# Main.net
KiCad netlist of a schematic drawn in Altium Designer
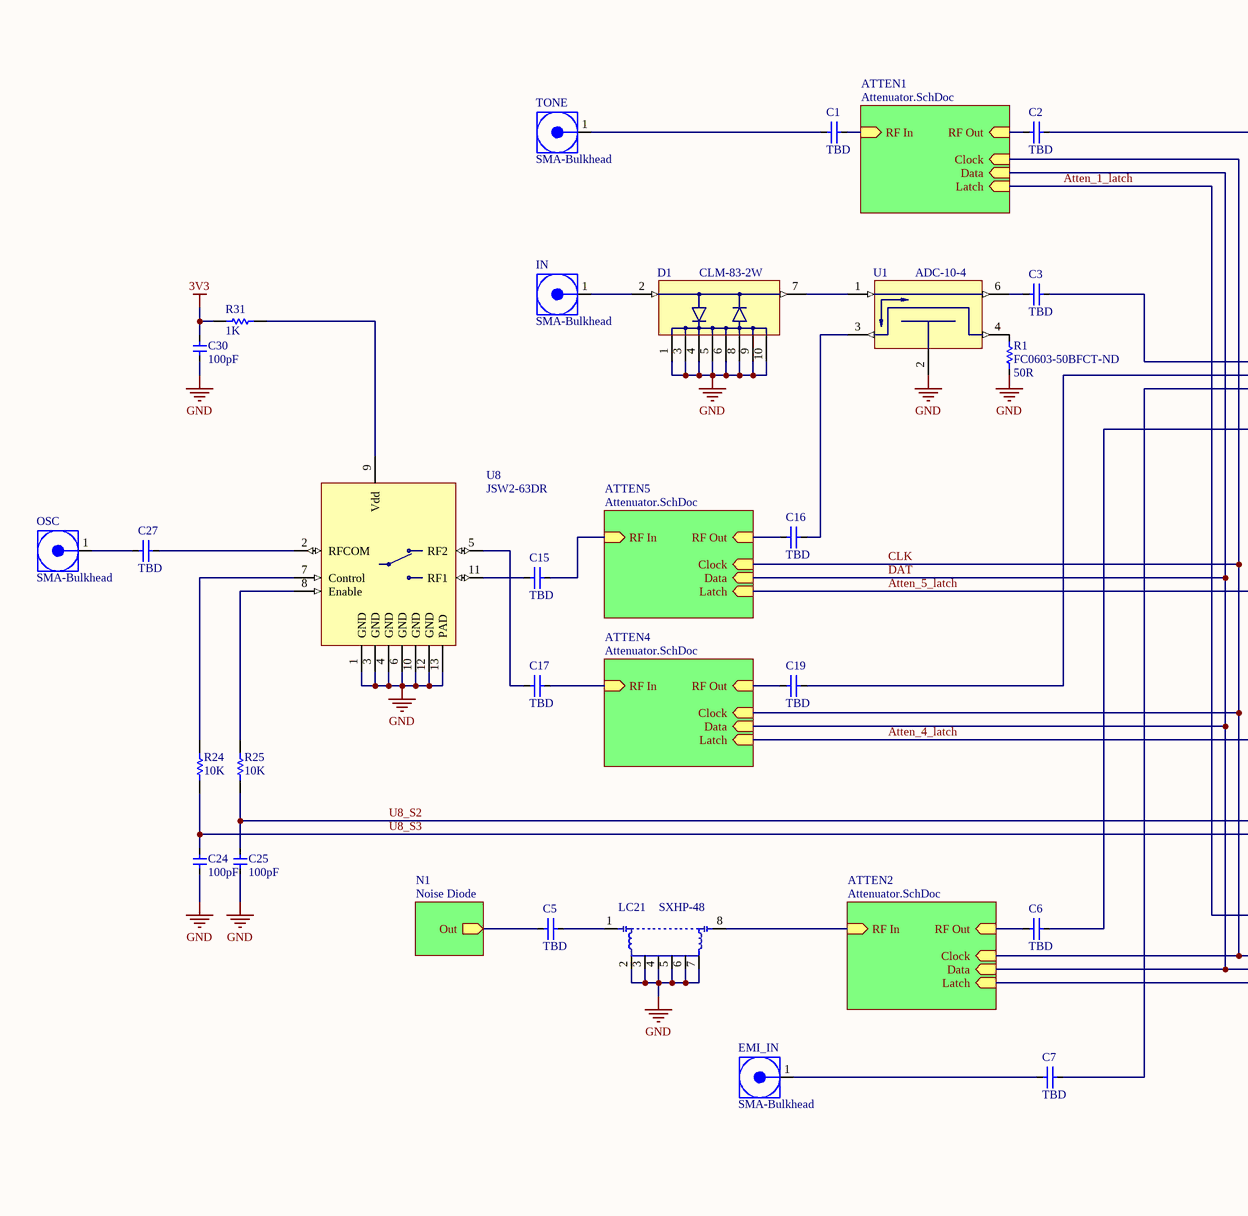
[diagram p0: Main.SchDoc, left]
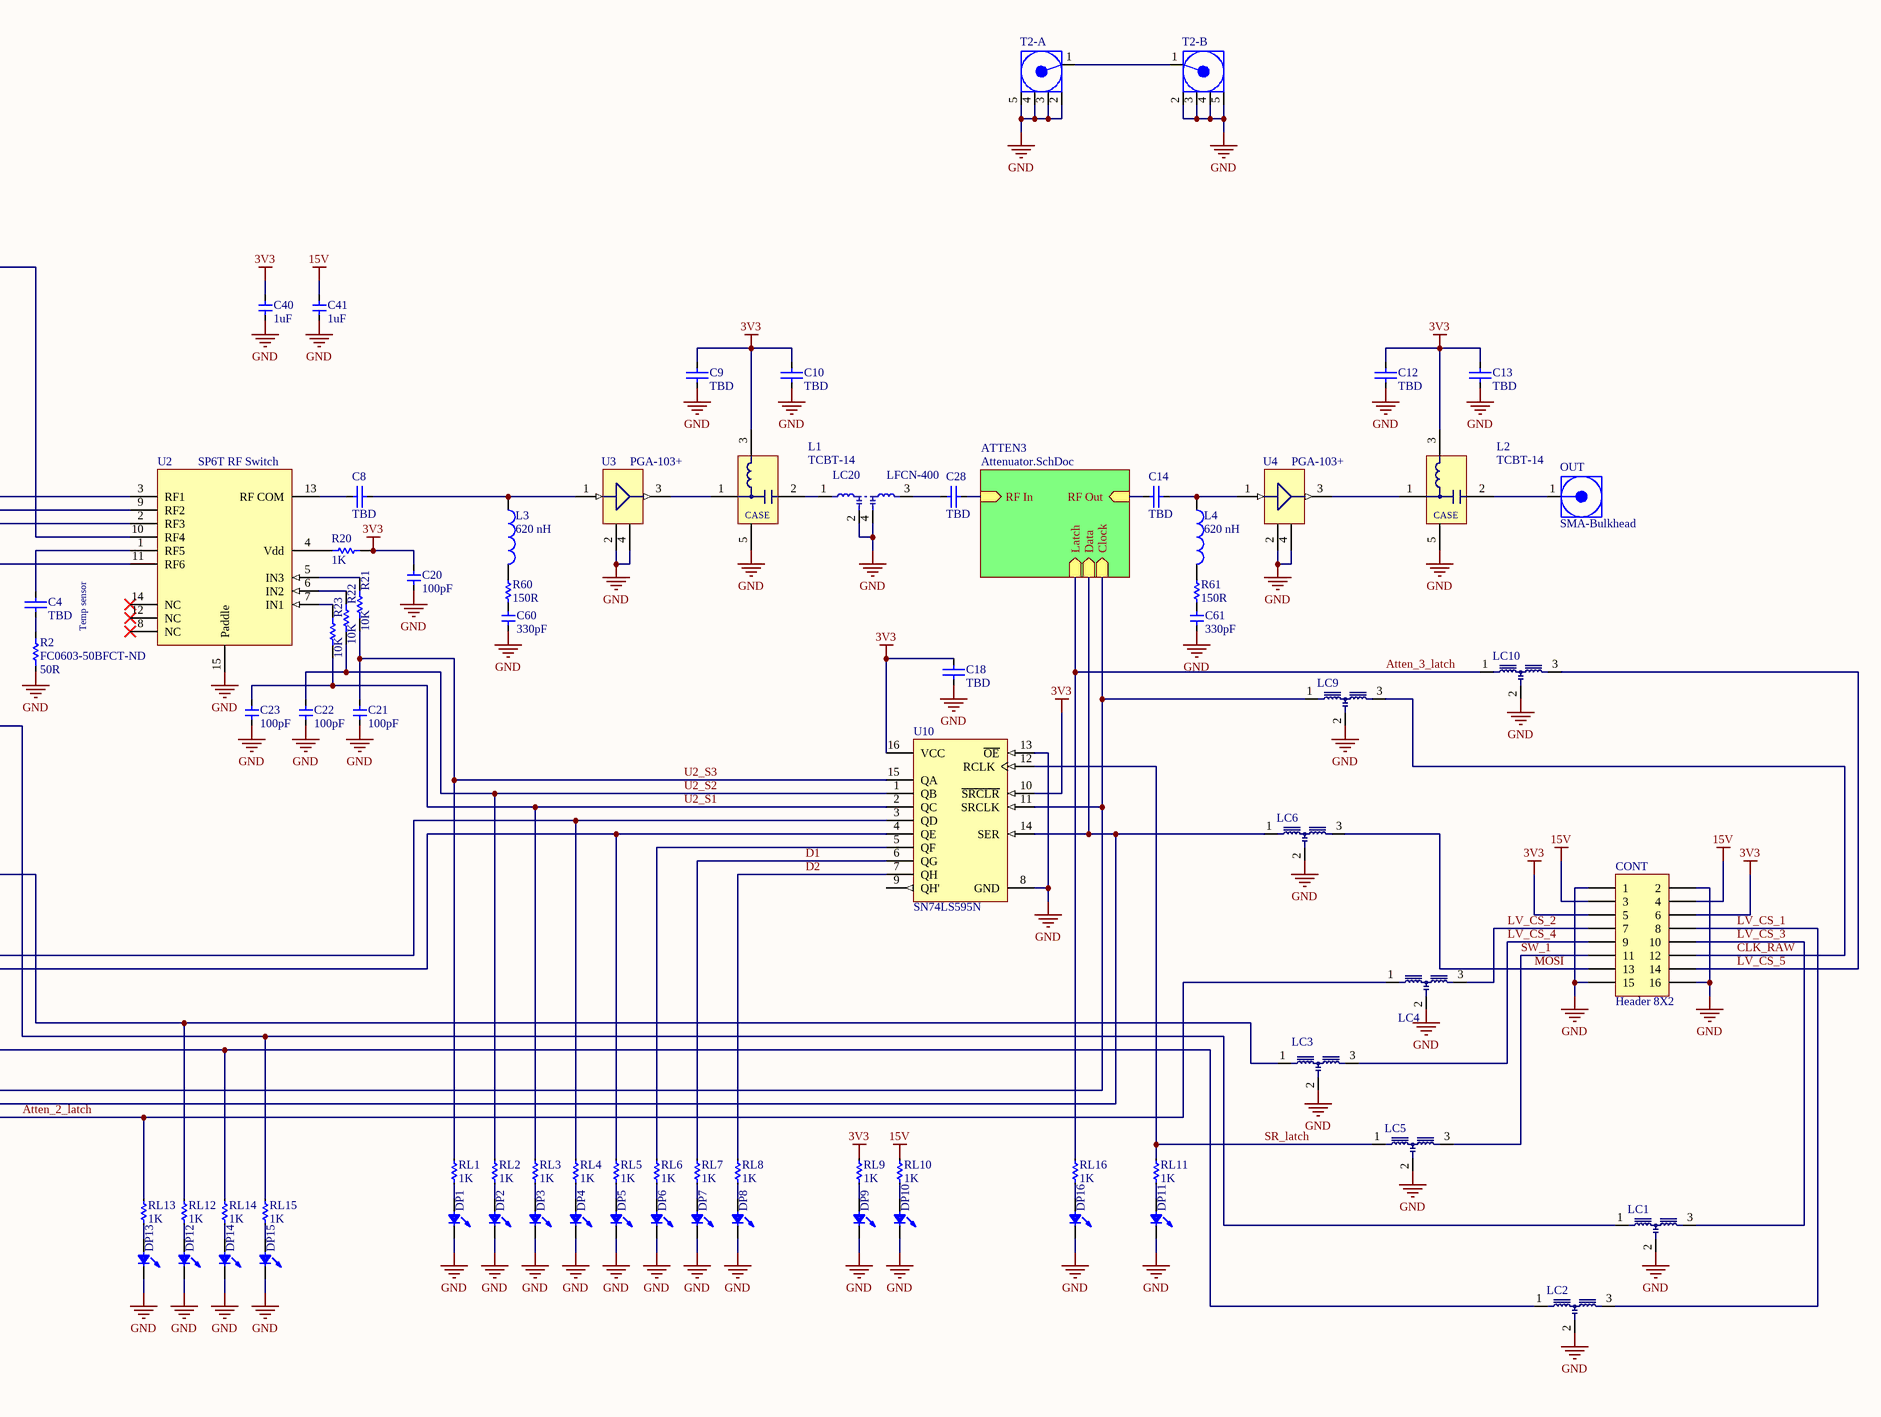
[diagram p1: Main.SchDoc, right]

(export (version "E")
  (design (tool "Eeschema 10.0.6"))
  (components
    (comp (ref "C1")
      (value "TBD")
      (footprint "0402C")
      (description "Capacitor")
      (fields (field (name "Comment") "Cap") (field (name "PUBLISHER") "Altium Limited"))
      (libsource (lib "Miscellaneous Devices") (part "Cap"))
    )
    (comp (ref "C2")
      (value "TBD")
      (footprint "0402C")
      (description "Capacitor")
      (fields (field (name "Comment") "Cap") (field (name "PUBLISHER") "Altium Limited"))
      (libsource (lib "Miscellaneous Devices") (part "Cap"))
    )
    (comp (ref "C3")
      (value "TBD")
      (footprint "0402C")
      (description "Capacitor")
      (fields (field (name "Comment") "Cap") (field (name "PUBLISHER") "Altium Limited"))
      (libsource (lib "Miscellaneous Devices") (part "Cap"))
    )
    (comp (ref "C4")
      (value "TBD")
      (footprint "0402C")
      (description "Capacitor")
      (fields (field (name "Comment") "Cap") (field (name "PUBLISHER") "Altium Limited"))
      (libsource (lib "Miscellaneous Devices") (part "Cap"))
    )
    (comp (ref "C5")
      (value "TBD")
      (footprint "0402C")
      (description "Capacitor")
      (fields (field (name "Comment") "Cap") (field (name "PUBLISHER") "Altium Limited"))
      (libsource (lib "Miscellaneous Devices") (part "Cap"))
    )
    (comp (ref "C6")
      (value "TBD")
      (footprint "0402C")
      (description "Capacitor")
      (fields (field (name "Comment") "Cap") (field (name "PUBLISHER") "Altium Limited"))
      (libsource (lib "Miscellaneous Devices") (part "Cap"))
    )
    (comp (ref "C7")
      (value "TBD")
      (footprint "0402C")
      (description "Capacitor")
      (fields (field (name "Comment") "Cap") (field (name "PUBLISHER") "Altium Limited"))
      (libsource (lib "Miscellaneous Devices") (part "Cap"))
    )
    (comp (ref "C8")
      (value "TBD")
      (footprint "0402C")
      (description "Capacitor")
      (fields (field (name "Comment") "Cap") (field (name "PUBLISHER") "Altium Limited"))
      (libsource (lib "Miscellaneous Devices") (part "Cap"))
    )
    (comp (ref "C9")
      (value "TBD")
      (footprint "0805C")
      (description "Capacitor")
      (fields (field (name "Comment") "Cap") (field (name "PUBLISHER") "Altium Limited"))
      (libsource (lib "Miscellaneous Devices") (part "Cap"))
    )
    (comp (ref "C10")
      (value "TBD")
      (footprint "0805C")
      (description "Capacitor")
      (fields (field (name "Comment") "Cap") (field (name "PUBLISHER") "Altium Limited"))
      (libsource (lib "Miscellaneous Devices") (part "Cap"))
    )
    (comp (ref "C12")
      (value "TBD")
      (footprint "0805C")
      (description "Capacitor")
      (fields (field (name "Comment") "Cap") (field (name "PUBLISHER") "Altium Limited"))
      (libsource (lib "Miscellaneous Devices") (part "Cap"))
    )
    (comp (ref "C13")
      (value "TBD")
      (footprint "0805C")
      (description "Capacitor")
      (fields (field (name "Comment") "Cap") (field (name "PUBLISHER") "Altium Limited"))
      (libsource (lib "Miscellaneous Devices") (part "Cap"))
    )
    (comp (ref "C14")
      (value "TBD")
      (footprint "0402C")
      (description "Capacitor")
      (fields (field (name "Comment") "Cap") (field (name "PUBLISHER") "Altium Limited"))
      (libsource (lib "Miscellaneous Devices") (part "Cap"))
    )
    (comp (ref "C15")
      (value "TBD")
      (footprint "0402C")
      (description "Capacitor")
      (fields (field (name "Comment") "Cap") (field (name "PUBLISHER") "Altium Limited"))
      (libsource (lib "Miscellaneous Devices") (part "Cap"))
    )
    (comp (ref "C16")
      (value "TBD")
      (footprint "0402C")
      (description "Capacitor")
      (fields (field (name "Comment") "Cap") (field (name "PUBLISHER") "Altium Limited"))
      (libsource (lib "Miscellaneous Devices") (part "Cap"))
    )
    (comp (ref "C17")
      (value "TBD")
      (footprint "0402C")
      (description "Capacitor")
      (fields (field (name "Comment") "Cap") (field (name "PUBLISHER") "Altium Limited"))
      (libsource (lib "Miscellaneous Devices") (part "Cap"))
    )
    (comp (ref "C18")
      (value "TBD")
      (footprint "0603C")
      (description "Capacitor")
      (fields (field (name "Comment") "Cap") (field (name "PUBLISHER") "Altium Limited"))
      (libsource (lib "Miscellaneous Devices") (part "Cap"))
    )
    (comp (ref "C19")
      (value "TBD")
      (footprint "0402C")
      (description "Capacitor")
      (fields (field (name "Comment") "Cap") (field (name "PUBLISHER") "Altium Limited"))
      (libsource (lib "Miscellaneous Devices") (part "Cap"))
    )
    (comp (ref "C20")
      (value "100pF")
      (footprint "0603C")
      (description "SMT Cap")
      (fields (field (name "PUBLISHER") "Altium Limited"))
      (libsource (lib "Miscellaneous Devices") (part "Cap - SMT Small"))
    )
    (comp (ref "C21")
      (value "100pF")
      (footprint "0603C")
      (description "SMT Cap")
      (fields (field (name "PUBLISHER") "Altium Limited"))
      (libsource (lib "Miscellaneous Devices") (part "Cap - SMT Small"))
    )
    (comp (ref "C22")
      (value "100pF")
      (footprint "0603C")
      (description "SMT Cap")
      (fields (field (name "PUBLISHER") "Altium Limited"))
      (libsource (lib "Miscellaneous Devices") (part "Cap - SMT Small"))
    )
    (comp (ref "C23")
      (value "100pF")
      (footprint "0603C")
      (description "SMT Cap")
      (fields (field (name "PUBLISHER") "Altium Limited"))
      (libsource (lib "Miscellaneous Devices") (part "Cap - SMT Small"))
    )
    (comp (ref "C24")
      (value "100pF")
      (footprint "0603C")
      (description "SMT Cap")
      (fields (field (name "PUBLISHER") "Altium Limited"))
      (libsource (lib "Miscellaneous Devices") (part "Cap - SMT Small"))
    )
    (comp (ref "C25")
      (value "100pF")
      (footprint "0603C")
      (description "SMT Cap")
      (fields (field (name "PUBLISHER") "Altium Limited"))
      (libsource (lib "Miscellaneous Devices") (part "Cap - SMT Small"))
    )
    (comp (ref "C27")
      (value "TBD")
      (footprint "0402C")
      (description "Capacitor")
      (fields (field (name "Comment") "Cap") (field (name "PUBLISHER") "Altium Limited"))
      (libsource (lib "Miscellaneous Devices") (part "Cap"))
    )
    (comp (ref "C28")
      (value "TBD")
      (footprint "0402C")
      (description "Capacitor")
      (fields (field (name "Comment") "Cap") (field (name "PUBLISHER") "Altium Limited"))
      (libsource (lib "Miscellaneous Devices") (part "Cap"))
    )
    (comp (ref "C30")
      (value "100pF")
      (footprint "0603C")
      (description "SMT Cap")
      (fields (field (name "PUBLISHER") "Altium Limited"))
      (libsource (lib "Miscellaneous Devices") (part "Cap - SMT Small"))
    )
    (comp (ref "C40")
      (value "1uF")
      (footprint "V")
      (description "SMT Cap")
      (fields (field (name "PUBLISHER") "Altium Limited"))
      (libsource (lib "Miscellaneous Devices") (part "Cap - SMT Small"))
    )
    (comp (ref "C41")
      (value "1uF")
      (footprint "V")
      (description "SMT Cap")
      (fields (field (name "PUBLISHER") "Altium Limited"))
      (libsource (lib "Miscellaneous Devices") (part "Cap - SMT Small"))
    )
    (comp (ref "C60")
      (value "330pF")
      (footprint "0603C")
      (description "SMT Cap")
      (fields (field (name "PUBLISHER") "Altium Limited"))
      (libsource (lib "Miscellaneous Devices") (part "Cap - SMT Small"))
    )
    (comp (ref "C61")
      (value "330pF")
      (footprint "0603C")
      (description "SMT Cap")
      (fields (field (name "PUBLISHER") "Altium Limited"))
      (libsource (lib "Miscellaneous Devices") (part "Cap - SMT Small"))
    )
    (comp (ref "CONT")
      (value "Header 8X2")
      (footprint "5103310-3")
      (description "Header, 8-Pin, Dual row")
      (fields (field (name "PUBLISHER") "Altium Limited"))
      (libsource (lib "Miscellaneous Connectors") (part "Header 8X2"))
    )
    (comp (ref "D1")
      (value "CLM-83-2W")
      (footprint "DL1721")
      (description "+12 to +32 dBm RF Limiter")
      (libsource (lib "RF Components") (part "CLM-83-2W"))
    )
    (comp (ref "DP1")
      (value "LED0")
      (footprint "0603 SMT LED")
      (description "T 1 3/4 LED")
      (fields (field (name "PUBLISHER") "Altium Limited"))
      (libsource (lib "Miscellaneous Devices") (part "LED0"))
    )
    (comp (ref "DP2")
      (value "LED0")
      (footprint "0603 SMT LED")
      (description "T 1 3/4 LED")
      (fields (field (name "PUBLISHER") "Altium Limited"))
      (libsource (lib "Miscellaneous Devices") (part "LED0"))
    )
    (comp (ref "DP3")
      (value "LED0")
      (footprint "0603 SMT LED")
      (description "T 1 3/4 LED")
      (fields (field (name "PUBLISHER") "Altium Limited"))
      (libsource (lib "Miscellaneous Devices") (part "LED0"))
    )
    (comp (ref "DP4")
      (value "LED0")
      (footprint "0603 SMT LED")
      (description "T 1 3/4 LED")
      (fields (field (name "PUBLISHER") "Altium Limited"))
      (libsource (lib "Miscellaneous Devices") (part "LED0"))
    )
    (comp (ref "DP5")
      (value "LED0")
      (footprint "0603 SMT LED")
      (description "T 1 3/4 LED")
      (fields (field (name "PUBLISHER") "Altium Limited"))
      (libsource (lib "Miscellaneous Devices") (part "LED0"))
    )
    (comp (ref "DP6")
      (value "LED0")
      (footprint "0603 SMT LED")
      (description "T 1 3/4 LED")
      (fields (field (name "PUBLISHER") "Altium Limited"))
      (libsource (lib "Miscellaneous Devices") (part "LED0"))
    )
    (comp (ref "DP7")
      (value "LED0")
      (footprint "0603 SMT LED")
      (description "T 1 3/4 LED")
      (fields (field (name "PUBLISHER") "Altium Limited"))
      (libsource (lib "Miscellaneous Devices") (part "LED0"))
    )
    (comp (ref "DP8")
      (value "LED0")
      (footprint "0603 SMT LED")
      (description "T 1 3/4 LED")
      (fields (field (name "PUBLISHER") "Altium Limited"))
      (libsource (lib "Miscellaneous Devices") (part "LED0"))
    )
    (comp (ref "DP9")
      (value "LED0")
      (footprint "0603 SMT LED")
      (description "T 1 3/4 LED")
      (fields (field (name "PUBLISHER") "Altium Limited"))
      (libsource (lib "Miscellaneous Devices") (part "LED0"))
    )
    (comp (ref "DP10")
      (value "LED0")
      (footprint "0603 SMT LED")
      (description "T 1 3/4 LED")
      (fields (field (name "PUBLISHER") "Altium Limited"))
      (libsource (lib "Miscellaneous Devices") (part "LED0"))
    )
    (comp (ref "DP11")
      (value "LED0")
      (footprint "0603 SMT LED")
      (description "T 1 3/4 LED")
      (fields (field (name "PUBLISHER") "Altium Limited"))
      (libsource (lib "Miscellaneous Devices") (part "LED0"))
    )
    (comp (ref "DP12")
      (value "LED0")
      (footprint "0603 SMT LED")
      (description "T 1 3/4 LED")
      (fields (field (name "PUBLISHER") "Altium Limited"))
      (libsource (lib "Miscellaneous Devices") (part "LED0"))
    )
    (comp (ref "DP13")
      (value "LED0")
      (footprint "0603 SMT LED")
      (description "T 1 3/4 LED")
      (fields (field (name "PUBLISHER") "Altium Limited"))
      (libsource (lib "Miscellaneous Devices") (part "LED0"))
    )
    (comp (ref "DP14")
      (value "LED0")
      (footprint "0603 SMT LED")
      (description "T 1 3/4 LED")
      (fields (field (name "PUBLISHER") "Altium Limited"))
      (libsource (lib "Miscellaneous Devices") (part "LED0"))
    )
    (comp (ref "DP15")
      (value "LED0")
      (footprint "0603 SMT LED")
      (description "T 1 3/4 LED")
      (fields (field (name "PUBLISHER") "Altium Limited"))
      (libsource (lib "Miscellaneous Devices") (part "LED0"))
    )
    (comp (ref "DP16")
      (value "LED0")
      (footprint "0603 SMT LED")
      (description "T 1 3/4 LED")
      (fields (field (name "PUBLISHER") "Altium Limited"))
      (libsource (lib "Miscellaneous Devices") (part "LED0"))
    )
    (comp (ref "EMI_IN")
      (value "SMA-Bulkhead")
      (footprint "1052902-1")
      (description "SMA Connector - Bulkhead")
      (libsource (lib "RF Components") (part "SMA-Bulkhead"))
    )
    (comp (ref "IN")
      (value "SMA-Bulkhead")
      (footprint "1052902-1")
      (description "SMA Connector - Bulkhead")
      (libsource (lib "RF Components") (part "SMA-Bulkhead"))
    )
    (comp (ref "L1")
      (value "TCBT-14")
      (footprint "GU1414")
      (description "Surface Mount 10 MHz to 10 GHz Bias Tee")
      (libsource (lib "RF Components") (part "TCBT-14"))
    )
    (comp (ref "L2")
      (value "TCBT-14")
      (footprint "GU1414")
      (description "Surface Mount 10 MHz to 10 GHz Bias Tee")
      (libsource (lib "RF Components") (part "TCBT-14"))
    )
    (comp (ref "L3")
      (value "620 nH")
      (footprint "1008L")
      (description "Inductor")
      (fields (field (name "PUBLISHER") "Altium Limited"))
      (libsource (lib "Miscellaneous Devices") (part "Inductor"))
    )
    (comp (ref "L4")
      (value "620 nH")
      (footprint "1008L")
      (description "Inductor")
      (fields (field (name "PUBLISHER") "Altium Limited"))
      (libsource (lib "Miscellaneous Devices") (part "Inductor"))
    )
    (comp (ref "LC1")
      (value "MEM2012F")
      (footprint "MEM2012S LC Filter")
      (description "Signal Line 3-terminal Filters")
      (libsource (lib "Unsorted") (part "MEM2012F - Signal Filter"))
    )
    (comp (ref "LC2")
      (value "MEM2012F")
      (footprint "MEM2012S LC Filter")
      (description "Signal Line 3-terminal Filters")
      (libsource (lib "Unsorted") (part "MEM2012F - Signal Filter"))
    )
    (comp (ref "LC3")
      (value "MEM2012F")
      (footprint "MEM2012S LC Filter")
      (description "Signal Line 3-terminal Filters")
      (libsource (lib "Unsorted") (part "MEM2012F - Signal Filter"))
    )
    (comp (ref "LC4")
      (value "MEM2012F")
      (footprint "MEM2012S LC Filter")
      (description "Signal Line 3-terminal Filters")
      (libsource (lib "Unsorted") (part "MEM2012F - Signal Filter"))
    )
    (comp (ref "LC5")
      (value "MEM2012F")
      (footprint "MEM2012S LC Filter")
      (description "Signal Line 3-terminal Filters")
      (libsource (lib "Unsorted") (part "MEM2012F - Signal Filter"))
    )
    (comp (ref "LC6")
      (value "MEM2012F")
      (footprint "MEM2012S LC Filter")
      (description "Signal Line 3-terminal Filters")
      (libsource (lib "Unsorted") (part "MEM2012F - Signal Filter"))
    )
    (comp (ref "LC9")
      (value "MEM2012F")
      (footprint "MEM2012S LC Filter")
      (description "Signal Line 3-terminal Filters")
      (libsource (lib "Unsorted") (part "MEM2012F - Signal Filter"))
    )
    (comp (ref "LC10")
      (value "MEM2012F")
      (footprint "MEM2012S LC Filter")
      (description "Signal Line 3-terminal Filters")
      (libsource (lib "Unsorted") (part "MEM2012F - Signal Filter"))
    )
    (comp (ref "LC20")
      (value "LFCN-400")
      (footprint "FV1206")
      (description "Ceramic Low Pass Filter")
      (libsource (lib "RF Components") (part "LFCN-xxx Filter"))
    )
    (comp (ref "LC21")
      (value "SXHP-48")
      (footprint "HF1139")
      (description "Integrated High Pass Filter")
      (libsource (lib "RF Components") (part "SXHP-xx Filter"))
    )
    (comp (ref "OSC")
      (value "SMA-Bulkhead")
      (footprint "1052902-1")
      (description "SMA Connector - Bulkhead")
      (libsource (lib "RF Components") (part "SMA-Bulkhead"))
    )
    (comp (ref "OUT")
      (value "SMA-Bulkhead")
      (footprint "1052902-1")
      (description "SMA Connector - Bulkhead")
      (libsource (lib "RF Components") (part "SMA-Bulkhead"))
    )
    (comp (ref "R1")
      (value "FC0603-50BFCT-ND")
      (footprint "0603R")
      (fields (field (name "ALTIUM_VALUE") "50R") (field (name "PUBLISHER") "Altium Limited"))
      (libsource (lib "") (part "Res Semi_1"))
    )
    (comp (ref "R2")
      (value "FC0603-50BFCT-ND")
      (footprint "0603R")
      (fields (field (name "ALTIUM_VALUE") "50R") (field (name "PUBLISHER") "Altium Limited"))
      (libsource (lib "") (part "Res Semi_1"))
    )
    (comp (ref "R20")
      (value "1K")
      (footprint "0603R")
      (description "Semiconductor Resistor")
      (fields (field (name "Comment") "RES Semi") (field (name "PUBLISHER") "Altium Limited"))
      (libsource (lib "Miscellaneous Devices") (part "Res Semi"))
    )
    (comp (ref "R21")
      (value "10K")
      (footprint "0603R")
      (description "Semiconductor Resistor")
      (fields (field (name "Comment") "RES Semi") (field (name "PUBLISHER") "Altium Limited"))
      (libsource (lib "Miscellaneous Devices") (part "Res Semi"))
    )
    (comp (ref "R22")
      (value "10K")
      (footprint "0603R")
      (description "Semiconductor Resistor")
      (fields (field (name "Comment") "RES Semi") (field (name "PUBLISHER") "Altium Limited"))
      (libsource (lib "Miscellaneous Devices") (part "Res Semi"))
    )
    (comp (ref "R23")
      (value "10K")
      (footprint "0603R")
      (description "Semiconductor Resistor")
      (fields (field (name "Comment") "RES Semi") (field (name "PUBLISHER") "Altium Limited"))
      (libsource (lib "Miscellaneous Devices") (part "Res Semi"))
    )
    (comp (ref "R24")
      (value "10K")
      (footprint "0603R")
      (description "Semiconductor Resistor")
      (fields (field (name "Comment") "RES Semi") (field (name "PUBLISHER") "Altium Limited"))
      (libsource (lib "Miscellaneous Devices") (part "Res Semi"))
    )
    (comp (ref "R25")
      (value "10K")
      (footprint "0603R")
      (description "Semiconductor Resistor")
      (fields (field (name "Comment") "RES Semi") (field (name "PUBLISHER") "Altium Limited"))
      (libsource (lib "Miscellaneous Devices") (part "Res Semi"))
    )
    (comp (ref "R31")
      (value "1K")
      (footprint "0603R")
      (description "Semiconductor Resistor")
      (fields (field (name "Comment") "RES Semi") (field (name "PUBLISHER") "Altium Limited"))
      (libsource (lib "Miscellaneous Devices") (part "Res Semi"))
    )
    (comp (ref "R60")
      (value "150R")
      (footprint "0603R")
      (description "Semiconductor Resistor")
      (fields (field (name "Comment") "Res Semi Small") (field (name "PUBLISHER") "Altium Limited"))
      (libsource (lib "Miscellaneous Devices") (part "Res Semi Small"))
    )
    (comp (ref "R61")
      (value "150R")
      (footprint "0603R")
      (description "Semiconductor Resistor")
      (fields (field (name "Comment") "Res Semi Small") (field (name "PUBLISHER") "Altium Limited"))
      (libsource (lib "Miscellaneous Devices") (part "Res Semi Small"))
    )
    (comp (ref "RL1")
      (value "1K")
      (footprint "0603R")
      (description "Semiconductor Resistor")
      (fields (field (name "Comment") "Res Semi Small") (field (name "PUBLISHER") "Altium Limited"))
      (libsource (lib "Miscellaneous Devices") (part "Res Semi Small"))
    )
    (comp (ref "RL2")
      (value "1K")
      (footprint "0603R")
      (description "Semiconductor Resistor")
      (fields (field (name "Comment") "Res Semi Small") (field (name "PUBLISHER") "Altium Limited"))
      (libsource (lib "Miscellaneous Devices") (part "Res Semi Small"))
    )
    (comp (ref "RL3")
      (value "1K")
      (footprint "0603R")
      (description "Semiconductor Resistor")
      (fields (field (name "Comment") "Res Semi Small") (field (name "PUBLISHER") "Altium Limited"))
      (libsource (lib "Miscellaneous Devices") (part "Res Semi Small"))
    )
    (comp (ref "RL4")
      (value "1K")
      (footprint "0603R")
      (description "Semiconductor Resistor")
      (fields (field (name "Comment") "Res Semi Small") (field (name "PUBLISHER") "Altium Limited"))
      (libsource (lib "Miscellaneous Devices") (part "Res Semi Small"))
    )
    (comp (ref "RL5")
      (value "1K")
      (footprint "0603R")
      (description "Semiconductor Resistor")
      (fields (field (name "Comment") "Res Semi Small") (field (name "PUBLISHER") "Altium Limited"))
      (libsource (lib "Miscellaneous Devices") (part "Res Semi Small"))
    )
    (comp (ref "RL6")
      (value "1K")
      (footprint "0603R")
      (description "Semiconductor Resistor")
      (fields (field (name "Comment") "Res Semi Small") (field (name "PUBLISHER") "Altium Limited"))
      (libsource (lib "Miscellaneous Devices") (part "Res Semi Small"))
    )
    (comp (ref "RL7")
      (value "1K")
      (footprint "0603R")
      (description "Semiconductor Resistor")
      (fields (field (name "Comment") "Res Semi Small") (field (name "PUBLISHER") "Altium Limited"))
      (libsource (lib "Miscellaneous Devices") (part "Res Semi Small"))
    )
    (comp (ref "RL8")
      (value "1K")
      (footprint "0603R")
      (description "Semiconductor Resistor")
      (fields (field (name "Comment") "Res Semi Small") (field (name "PUBLISHER") "Altium Limited"))
      (libsource (lib "Miscellaneous Devices") (part "Res Semi Small"))
    )
    (comp (ref "RL9")
      (value "1K")
      (footprint "0603R")
      (description "Semiconductor Resistor")
      (fields (field (name "Comment") "Res Semi Small") (field (name "PUBLISHER") "Altium Limited"))
      (libsource (lib "Miscellaneous Devices") (part "Res Semi Small"))
    )
    (comp (ref "RL10")
      (value "1K")
      (footprint "0603R")
      (description "Semiconductor Resistor")
      (fields (field (name "Comment") "Res Semi Small") (field (name "PUBLISHER") "Altium Limited"))
      (libsource (lib "Miscellaneous Devices") (part "Res Semi Small"))
    )
    (comp (ref "RL11")
      (value "1K")
      (footprint "0603R")
      (description "Semiconductor Resistor")
      (fields (field (name "Comment") "Res Semi Small") (field (name "PUBLISHER") "Altium Limited"))
      (libsource (lib "Miscellaneous Devices") (part "Res Semi Small"))
    )
    (comp (ref "RL12")
      (value "1K")
      (footprint "0603R")
      (description "Semiconductor Resistor")
      (fields (field (name "Comment") "Res Semi Small") (field (name "PUBLISHER") "Altium Limited"))
      (libsource (lib "Miscellaneous Devices") (part "Res Semi Small"))
    )
    (comp (ref "RL13")
      (value "1K")
      (footprint "0603R")
      (description "Semiconductor Resistor")
      (fields (field (name "Comment") "Res Semi Small") (field (name "PUBLISHER") "Altium Limited"))
      (libsource (lib "Miscellaneous Devices") (part "Res Semi Small"))
    )
    (comp (ref "RL14")
      (value "1K")
      (footprint "0603R")
      (description "Semiconductor Resistor")
      (fields (field (name "Comment") "Res Semi Small") (field (name "PUBLISHER") "Altium Limited"))
      (libsource (lib "Miscellaneous Devices") (part "Res Semi Small"))
    )
    (comp (ref "RL15")
      (value "1K")
      (footprint "0603R")
      (description "Semiconductor Resistor")
      (fields (field (name "Comment") "Res Semi Small") (field (name "PUBLISHER") "Altium Limited"))
      (libsource (lib "Miscellaneous Devices") (part "Res Semi Small"))
    )
    (comp (ref "RL16")
      (value "1K")
      (footprint "0603R")
      (description "Semiconductor Resistor")
      (fields (field (name "Comment") "Res Semi Small") (field (name "PUBLISHER") "Altium Limited"))
      (libsource (lib "Miscellaneous Devices") (part "Res Semi Small"))
    )
    (comp (ref "T2-A")
      (value "COAX-M")
      (footprint "SMT RA SMA Connector")
      (description "RF Coaxial PCB Connector, MMCX; Thru-Hole, Vertical Mount Plug,  50 Ohm Impedance")
      (fields (field (name "PUBLISHER") "Altium Limited"))
      (libsource (lib "Miscellaneous Connectors") (part "COAX-M"))
    )
    (comp (ref "T2-B")
      (value "COAX-M")
      (footprint "SMT RA SMA Connector")
      (description "RF Coaxial PCB Connector, MMCX; Thru-Hole, Vertical Mount Plug,  50 Ohm Impedance")
      (fields (field (name "PUBLISHER") "Altium Limited"))
      (libsource (lib "Miscellaneous Connectors") (part "COAX-M"))
    )
    (comp (ref "TONE")
      (value "SMA-Bulkhead")
      (footprint "1052902-1")
      (description "SMA Connector - Bulkhead")
      (libsource (lib "RF Components") (part "SMA-Bulkhead"))
    )
    (comp (ref "U1")
      (value "ADC-10-4")
      (footprint "CD542")
      (description "Surface Mount Directional Coupler")
      (libsource (lib "RF Components") (part "ADC-10-4"))
    )
    (comp (ref "U2")
      (value "SP6T RF Switch")
      (footprint "MT1817")
      (description "SP6T RF Switch 50Ω 10 to 2700 MHz")
      (libsource (lib "RF Components") (part "JSW6-33DR+"))
    )
    (comp (ref "U3")
      (value "PGA-103+")
      (footprint "DF782")
      (description "Ultra Linear Low Noise Monolithic Amplifier")
      (libsource (lib "RF Components") (part "PGA-103+"))
    )
    (comp (ref "U4")
      (value "PGA-103+")
      (footprint "DF782")
      (description "Ultra Linear Low Noise Monolithic Amplifier")
      (libsource (lib "RF Components") (part "PGA-103+"))
    )
    (comp (ref "U8")
      (value "JSW2-63DR")
      (footprint "MT1818")
      (description "SPDT RF Switch")
      (libsource (lib "RF Components") (part "JSW2-63DR"))
    )
    (comp (ref "U10")
      (value "SN74LS595N")
      (footprint "SOIC127P602-16BN")
      (description "8-Bit Shift Register with Output Latch")
      (fields (field (name "PUBLISHER") "Altium Limited"))
      (libsource (lib "TI Logic Register") (part "SN74LS595N"))
    )
  )
  (nets
    (net (code "1") (name "/Atten_1_latch") (class "Default")
      (node (ref "LC2") (pin "1") (pinfunction "1_1") (pintype "passive"))
      (node (ref "RL14") (pin "1") (pinfunction "1_1") (pintype "passive"))
    )
    (net (code "2") (name "/Atten_2_latch") (class "Default")
      (node (ref "LC4") (pin "1") (pinfunction "1_1") (pintype "passive"))
      (node (ref "RL13") (pin "1") (pinfunction "1_1") (pintype "passive"))
    )
    (net (code "3") (name "/Atten_3_latch") (class "Default")
      (node (ref "LC10") (pin "1") (pinfunction "1_1") (pintype "passive"))
      (node (ref "RL16") (pin "1") (pinfunction "1_1") (pintype "passive"))
    )
    (net (code "4") (name "/Atten_4_latch") (class "Default")
      (node (ref "LC3") (pin "1") (pinfunction "1_1") (pintype "passive"))
      (node (ref "RL12") (pin "1") (pinfunction "1_1") (pintype "passive"))
    )
    (net (code "5") (name "/Atten_5_latch") (class "Default")
      (node (ref "LC1") (pin "1") (pinfunction "1_1") (pintype "passive"))
      (node (ref "RL15") (pin "1") (pinfunction "1_1") (pintype "passive"))
    )
    (net (code "6") (name "/CLK") (class "Default")
      (node (ref "LC9") (pin "1") (pinfunction "1_1") (pintype "passive"))
      (node (ref "U10") (pin "11") (pinfunction "SRCLK_11") (pintype "input"))
    )
    (net (code "7") (name "/CLK_RAW") (class "Default")
      (node (ref "CONT") (pin "12") (pinfunction "12_12") (pintype "passive"))
      (node (ref "LC9") (pin "3") (pinfunction "3_3") (pintype "passive"))
    )
    (net (code "8") (name "/D1") (class "Default")
      (node (ref "RL7") (pin "1") (pinfunction "1_1") (pintype "passive"))
      (node (ref "U10") (pin "6") (pinfunction "QG_6") (pintype "tri_state"))
    )
    (net (code "9") (name "/D2") (class "Default")
      (node (ref "RL8") (pin "1") (pinfunction "1_1") (pintype "passive"))
      (node (ref "U10") (pin "7") (pinfunction "QH_7") (pintype "tri_state"))
    )
    (net (code "10") (name "/DAT") (class "Default")
      (node (ref "LC6") (pin "1") (pinfunction "1_1") (pintype "passive"))
      (node (ref "U10") (pin "14") (pinfunction "SER_14") (pintype "input"))
    )
    (net (code "11") (name "/LV_CS_1") (class "Default")
      (node (ref "CONT") (pin "8") (pinfunction "8_8") (pintype "passive"))
      (node (ref "LC2") (pin "3") (pinfunction "3_3") (pintype "passive"))
    )
    (net (code "12") (name "/LV_CS_2") (class "Default")
      (node (ref "CONT") (pin "7") (pinfunction "7_7") (pintype "passive"))
      (node (ref "LC4") (pin "3") (pinfunction "3_3") (pintype "passive"))
    )
    (net (code "13") (name "/LV_CS_3") (class "Default")
      (node (ref "CONT") (pin "10") (pinfunction "10_10") (pintype "passive"))
      (node (ref "LC1") (pin "3") (pinfunction "3_3") (pintype "passive"))
    )
    (net (code "14") (name "/LV_CS_4") (class "Default")
      (node (ref "CONT") (pin "9") (pinfunction "9_9") (pintype "passive"))
      (node (ref "LC3") (pin "3") (pinfunction "3_3") (pintype "passive"))
    )
    (net (code "15") (name "/LV_CS_5") (class "Default")
      (node (ref "CONT") (pin "14") (pinfunction "14_14") (pintype "passive"))
      (node (ref "LC10") (pin "3") (pinfunction "3_3") (pintype "passive"))
    )
    (net (code "16") (name "/MOSI") (class "Default")
      (node (ref "CONT") (pin "13") (pinfunction "13_13") (pintype "passive"))
      (node (ref "LC6") (pin "3") (pinfunction "3_3") (pintype "passive"))
    )
    (net (code "17") (name "/Out") (class "Default")
      (node (ref "C5") (pin "1") (pinfunction "1_1") (pintype "passive"))
    )
    (net (code "18") (name "/RF In") (class "Default") (node (ref "LC21") (pin "8") (pintype "passive")))
    (net (code "19") (name "/RF In_1") (class "Default")
      (node (ref "C28") (pin "2") (pinfunction "2_2") (pintype "passive"))
    )
    (net (code "20") (name "/RF In_2") (class "Default")
      (node (ref "C1") (pin "2") (pinfunction "2_2") (pintype "passive"))
    )
    (net (code "21") (name "/RF In_3") (class "Default")
      (node (ref "C15") (pin "2") (pinfunction "2_2") (pintype "passive"))
    )
    (net (code "22") (name "/RF In_4") (class "Default")
      (node (ref "C17") (pin "2") (pinfunction "2_2") (pintype "passive"))
    )
    (net (code "23") (name "/RF Out") (class "Default")
      (node (ref "C2") (pin "1") (pinfunction "1_1") (pintype "passive"))
    )
    (net (code "24") (name "/RF Out_1") (class "Default")
      (node (ref "C6") (pin "1") (pinfunction "1_1") (pintype "passive"))
    )
    (net (code "25") (name "/RF Out_2") (class "Default")
      (node (ref "C14") (pin "1") (pinfunction "1_1") (pintype "passive"))
    )
    (net (code "26") (name "/RF Out_3") (class "Default")
      (node (ref "C19") (pin "1") (pinfunction "1_1") (pintype "passive"))
    )
    (net (code "27") (name "/RF Out_4") (class "Default")
      (node (ref "C16") (pin "1") (pinfunction "1_1") (pintype "passive"))
    )
    (net (code "28") (name "/SR_latch") (class "Default")
      (node (ref "LC5") (pin "1") (pinfunction "1_1") (pintype "passive"))
      (node (ref "RL11") (pin "1") (pinfunction "1_1") (pintype "passive"))
      (node (ref "U10") (pin "12") (pinfunction "RCLK_12") (pintype "input"))
    )
    (net (code "29") (name "/SW_1") (class "Default")
      (node (ref "CONT") (pin "11") (pinfunction "11_11") (pintype "passive"))
      (node (ref "LC5") (pin "3") (pinfunction "3_3") (pintype "passive"))
    )
    (net (code "30") (name "/U2_S1") (class "Default")
      (node (ref "C23") (pin "2") (pinfunction "2_2") (pintype "passive"))
      (node (ref "R23") (pin "2") (pinfunction "2_2") (pintype "passive"))
      (node (ref "RL3") (pin "1") (pinfunction "1_1") (pintype "passive"))
      (node (ref "U10") (pin "2") (pinfunction "QC_2") (pintype "tri_state"))
    )
    (net (code "31") (name "/U2_S2") (class "Default")
      (node (ref "C22") (pin "2") (pinfunction "2_2") (pintype "passive"))
      (node (ref "R22") (pin "2") (pinfunction "2_2") (pintype "passive"))
      (node (ref "RL2") (pin "1") (pinfunction "1_1") (pintype "passive"))
      (node (ref "U10") (pin "1") (pinfunction "QB_1") (pintype "tri_state"))
    )
    (net (code "32") (name "/U2_S3") (class "Default")
      (node (ref "C21") (pin "2") (pinfunction "2_2") (pintype "passive"))
      (node (ref "R21") (pin "2") (pinfunction "2_2") (pintype "passive"))
      (node (ref "RL1") (pin "1") (pinfunction "1_1") (pintype "passive"))
      (node (ref "U10") (pin "15") (pinfunction "QA_15") (pintype "tri_state"))
    )
    (net (code "33") (name "/U8_S2") (class "Default")
      (node (ref "C25") (pin "2") (pinfunction "2_2") (pintype "passive"))
      (node (ref "R25") (pin "1") (pinfunction "1_1") (pintype "passive"))
      (node (ref "RL4") (pin "1") (pinfunction "1_1") (pintype "passive"))
      (node (ref "U10") (pin "3") (pinfunction "QD_3") (pintype "tri_state"))
    )
    (net (code "34") (name "/U8_S3") (class "Default")
      (node (ref "C24") (pin "2") (pinfunction "2_2") (pintype "passive"))
      (node (ref "R24") (pin "1") (pinfunction "1_1") (pintype "passive"))
      (node (ref "RL5") (pin "1") (pinfunction "1_1") (pintype "passive"))
      (node (ref "U10") (pin "4") (pinfunction "QE_4") (pintype "tri_state"))
    )
    (net (code "35") (name "3V3") (class "Default")
      (node (ref "C10") (pin "2") (pinfunction "2_2") (pintype "passive"))
      (node (ref "C12") (pin "2") (pinfunction "2_2") (pintype "passive"))
      (node (ref "C13") (pin "2") (pinfunction "2_2") (pintype "passive"))
      (node (ref "C18") (pin "2") (pinfunction "2_2") (pintype "passive"))
      (node (ref "C20") (pin "2") (pinfunction "2_2") (pintype "passive"))
      (node (ref "C30") (pin "2") (pinfunction "2_2") (pintype "passive"))
      (node (ref "C40") (pin "1") (pinfunction "1_1") (pintype "passive"))
      (node (ref "C9") (pin "2") (pinfunction "2_2") (pintype "passive"))
      (node (ref "CONT") (pin "5") (pinfunction "5_5") (pintype "passive"))
      (node (ref "CONT") (pin "6") (pinfunction "6_6") (pintype "passive"))
      (node (ref "L1") (pin "3") (pinfunction "DC_3") (pintype "passive"))
      (node (ref "L2") (pin "3") (pinfunction "DC_3") (pintype "passive"))
      (node (ref "R20") (pin "2") (pinfunction "2_2") (pintype "passive"))
      (node (ref "R31") (pin "2") (pinfunction "2_2") (pintype "passive"))
      (node (ref "RL9") (pin "1") (pinfunction "1_1") (pintype "passive"))
      (node (ref "U10") (pin "10") (pinfunction "~{SRCLR}_10") (pintype "input"))
      (node (ref "U10") (pin "16") (pinfunction "VCC_16") (pintype "power_in"))
    )
    (net (code "36") (name "15V") (class "Default")
      (node (ref "C41") (pin "1") (pinfunction "1_1") (pintype "passive"))
      (node (ref "CONT") (pin "3") (pinfunction "3_3") (pintype "passive"))
      (node (ref "CONT") (pin "4") (pinfunction "4_4") (pintype "passive"))
      (node (ref "RL10") (pin "1") (pinfunction "1_1") (pintype "passive"))
    )
    (net (code "37") (name "GND") (class "Default")
      (node (ref "C10") (pin "1") (pinfunction "1_1") (pintype "passive"))
      (node (ref "C12") (pin "1") (pinfunction "1_1") (pintype "passive"))
      (node (ref "C13") (pin "1") (pinfunction "1_1") (pintype "passive"))
      (node (ref "C18") (pin "1") (pinfunction "1_1") (pintype "passive"))
      (node (ref "C20") (pin "1") (pinfunction "1_1") (pintype "passive"))
      (node (ref "C21") (pin "1") (pinfunction "1_1") (pintype "passive"))
      (node (ref "C22") (pin "1") (pinfunction "1_1") (pintype "passive"))
      (node (ref "C23") (pin "1") (pinfunction "1_1") (pintype "passive"))
      (node (ref "C24") (pin "1") (pinfunction "1_1") (pintype "passive"))
      (node (ref "C25") (pin "1") (pinfunction "1_1") (pintype "passive"))
      (node (ref "C30") (pin "1") (pinfunction "1_1") (pintype "passive"))
      (node (ref "C40") (pin "2") (pinfunction "2_2") (pintype "passive"))
      (node (ref "C41") (pin "2") (pinfunction "2_2") (pintype "passive"))
      (node (ref "C60") (pin "2") (pinfunction "2_2") (pintype "passive"))
      (node (ref "C61") (pin "2") (pinfunction "2_2") (pintype "passive"))
      (node (ref "C9") (pin "1") (pinfunction "1_1") (pintype "passive"))
      (node (ref "CONT") (pin "1") (pinfunction "1_1") (pintype "passive"))
      (node (ref "CONT") (pin "15") (pinfunction "15_15") (pintype "passive"))
      (node (ref "CONT") (pin "16") (pinfunction "16_16") (pintype "passive"))
      (node (ref "CONT") (pin "2") (pinfunction "2_2") (pintype "passive"))
      (node (ref "D1") (pin "1") (pinfunction "Gnd_1") (pintype "passive"))
      (node (ref "D1") (pin "10") (pinfunction "Gnd_10") (pintype "power_in"))
      (node (ref "D1") (pin "3") (pinfunction "Gnd_3") (pintype "power_in"))
      (node (ref "D1") (pin "4") (pinfunction "Gnd_4") (pintype "power_in"))
      (node (ref "D1") (pin "5") (pinfunction "Gnd_5") (pintype "power_in"))
      (node (ref "D1") (pin "6") (pinfunction "Gnd_6") (pintype "power_in"))
      (node (ref "D1") (pin "8") (pinfunction "Gnd_8") (pintype "power_in"))
      (node (ref "D1") (pin "9") (pinfunction "Gnd_9") (pintype "power_in"))
      (node (ref "DP1") (pin "2") (pinfunction "2_2") (pintype "passive"))
      (node (ref "DP10") (pin "2") (pinfunction "2_2") (pintype "passive"))
      (node (ref "DP11") (pin "2") (pinfunction "2_2") (pintype "passive"))
      (node (ref "DP12") (pin "2") (pinfunction "2_2") (pintype "passive"))
      (node (ref "DP13") (pin "2") (pinfunction "2_2") (pintype "passive"))
      (node (ref "DP14") (pin "2") (pinfunction "2_2") (pintype "passive"))
      (node (ref "DP15") (pin "2") (pinfunction "2_2") (pintype "passive"))
      (node (ref "DP16") (pin "2") (pinfunction "2_2") (pintype "passive"))
      (node (ref "DP2") (pin "2") (pinfunction "2_2") (pintype "passive"))
      (node (ref "DP3") (pin "2") (pinfunction "2_2") (pintype "passive"))
      (node (ref "DP4") (pin "2") (pinfunction "2_2") (pintype "passive"))
      (node (ref "DP5") (pin "2") (pinfunction "2_2") (pintype "passive"))
      (node (ref "DP6") (pin "2") (pinfunction "2_2") (pintype "passive"))
      (node (ref "DP7") (pin "2") (pinfunction "2_2") (pintype "passive"))
      (node (ref "DP8") (pin "2") (pinfunction "2_2") (pintype "passive"))
      (node (ref "DP9") (pin "2") (pinfunction "2_2") (pintype "passive"))
      (node (ref "L1") (pin "5") (pinfunction "CASE_5") (pintype "passive"))
      (node (ref "L2") (pin "5") (pinfunction "CASE_5") (pintype "passive"))
      (node (ref "LC1") (pin "2") (pinfunction "2_2") (pintype "passive"))
      (node (ref "LC10") (pin "2") (pinfunction "2_2") (pintype "passive"))
      (node (ref "LC2") (pin "2") (pinfunction "2_2") (pintype "passive"))
      (node (ref "LC20") (pin "2") (pintype "passive"))
      (node (ref "LC20") (pin "4") (pintype "passive"))
      (node (ref "LC21") (pin "2") (pintype "passive"))
      (node (ref "LC21") (pin "3") (pinfunction "3_3") (pintype "power_in"))
      (node (ref "LC21") (pin "4") (pintype "passive"))
      (node (ref "LC21") (pin "5") (pinfunction "5_5") (pintype "power_in"))
      (node (ref "LC21") (pin "6") (pinfunction "6_6") (pintype "power_in"))
      (node (ref "LC21") (pin "7") (pinfunction "7_7") (pintype "power_in"))
      (node (ref "LC3") (pin "2") (pinfunction "2_2") (pintype "passive"))
      (node (ref "LC4") (pin "2") (pinfunction "2_2") (pintype "passive"))
      (node (ref "LC5") (pin "2") (pinfunction "2_2") (pintype "passive"))
      (node (ref "LC6") (pin "2") (pinfunction "2_2") (pintype "passive"))
      (node (ref "LC9") (pin "2") (pinfunction "2_2") (pintype "passive"))
      (node (ref "R1") (pin "1") (pinfunction "1_1") (pintype "passive"))
      (node (ref "R2") (pin "1") (pinfunction "1_1") (pintype "passive"))
      (node (ref "T2-A") (pin "2") (pinfunction "GND_2") (pintype "power_in"))
      (node (ref "T2-A") (pin "3") (pinfunction "GND_3") (pintype "power_in"))
      (node (ref "T2-A") (pin "4") (pinfunction "GND_4") (pintype "power_in"))
      (node (ref "T2-A") (pin "5") (pinfunction "GND_5") (pintype "power_in"))
      (node (ref "T2-B") (pin "2") (pinfunction "GND_2") (pintype "power_in"))
      (node (ref "T2-B") (pin "3") (pinfunction "GND_3") (pintype "power_in"))
      (node (ref "T2-B") (pin "4") (pinfunction "GND_4") (pintype "power_in"))
      (node (ref "T2-B") (pin "5") (pinfunction "GND_5") (pintype "power_in"))
      (node (ref "U1") (pin "2") (pinfunction "Gnd_2") (pintype "power_in"))
      (node (ref "U10") (pin "13") (pinfunction "~{OE}_13") (pintype "input"))
      (node (ref "U10") (pin "8") (pinfunction "GND_8") (pintype "power_in"))
      (node (ref "U2") (pin "15") (pinfunction "Paddle_15") (pintype "power_in"))
      (node (ref "U3") (pin "2") (pinfunction "Gnd_2") (pintype "passive"))
      (node (ref "U3") (pin "4") (pinfunction "Gnd_4") (pintype "power_in"))
      (node (ref "U4") (pin "2") (pinfunction "Gnd_2") (pintype "passive"))
      (node (ref "U4") (pin "4") (pinfunction "Gnd_4") (pintype "power_in"))
      (node (ref "U8") (pin "1") (pinfunction "GND_1") (pintype "power_in"))
      (node (ref "U8") (pin "10") (pinfunction "GND_10") (pintype "power_in"))
      (node (ref "U8") (pin "12") (pinfunction "GND_12") (pintype "power_in"))
      (node (ref "U8") (pin "13") (pinfunction "PAD_13") (pintype "power_in"))
      (node (ref "U8") (pin "3") (pinfunction "GND_3") (pintype "power_in"))
      (node (ref "U8") (pin "4") (pinfunction "GND_4") (pintype "power_in"))
      (node (ref "U8") (pin "6") (pinfunction "GND_6") (pintype "power_in"))
    )
    (net (code "38") (name "Net-(C4-Pad1)") (class "Default")
      (node (ref "C4") (pin "1") (pinfunction "1_1") (pintype "passive"))
      (node (ref "R2") (pin "2") (pinfunction "2_2") (pintype "passive"))
    )
    (net (code "39") (name "Net-(C5-Pad2)") (class "Default")
      (node (ref "C5") (pin "2") (pinfunction "2_2") (pintype "passive"))
      (node (ref "LC21") (pin "1") (pintype "passive"))
    )
    (net (code "40") (name "Net-(C28-Pad1)") (class "Default")
      (node (ref "C28") (pin "1") (pinfunction "1_1") (pintype "passive"))
      (node (ref "LC20") (pin "3") (pintype "passive"))
    )
    (net (code "41") (name "Net-(C60-Pad1)") (class "Default")
      (node (ref "C60") (pin "1") (pinfunction "1_1") (pintype "passive"))
      (node (ref "R60") (pin "2") (pinfunction "2_2") (pintype "passive"))
    )
    (net (code "42") (name "Net-(C61-Pad1)") (class "Default")
      (node (ref "C61") (pin "1") (pinfunction "1_1") (pintype "passive"))
      (node (ref "R61") (pin "2") (pinfunction "2_2") (pintype "passive"))
    )
    (net (code "43") (name "Net-(D1-In)") (class "Default")
      (node (ref "D1") (pin "2") (pinfunction "In_2") (pintype "input"))
      (node (ref "IN") (pin "1") (pinfunction "Signal_1") (pintype "passive"))
    )
    (net (code "44") (name "Net-(DP1-Pad1)") (class "Default")
      (node (ref "DP1") (pin "1") (pinfunction "1_1") (pintype "passive"))
      (node (ref "RL1") (pin "2") (pinfunction "2_2") (pintype "passive"))
    )
    (net (code "45") (name "Net-(DP2-Pad1)") (class "Default")
      (node (ref "DP2") (pin "1") (pinfunction "1_1") (pintype "passive"))
      (node (ref "RL2") (pin "2") (pinfunction "2_2") (pintype "passive"))
    )
    (net (code "46") (name "Net-(DP3-Pad1)") (class "Default")
      (node (ref "DP3") (pin "1") (pinfunction "1_1") (pintype "passive"))
      (node (ref "RL3") (pin "2") (pinfunction "2_2") (pintype "passive"))
    )
    (net (code "47") (name "Net-(DP4-Pad1)") (class "Default")
      (node (ref "DP4") (pin "1") (pinfunction "1_1") (pintype "passive"))
      (node (ref "RL4") (pin "2") (pinfunction "2_2") (pintype "passive"))
    )
    (net (code "48") (name "Net-(DP5-Pad1)") (class "Default")
      (node (ref "DP5") (pin "1") (pinfunction "1_1") (pintype "passive"))
      (node (ref "RL5") (pin "2") (pinfunction "2_2") (pintype "passive"))
    )
    (net (code "49") (name "Net-(DP6-Pad1)") (class "Default")
      (node (ref "DP6") (pin "1") (pinfunction "1_1") (pintype "passive"))
      (node (ref "RL6") (pin "2") (pinfunction "2_2") (pintype "passive"))
    )
    (net (code "50") (name "Net-(DP7-Pad1)") (class "Default")
      (node (ref "DP7") (pin "1") (pinfunction "1_1") (pintype "passive"))
      (node (ref "RL7") (pin "2") (pinfunction "2_2") (pintype "passive"))
    )
    (net (code "51") (name "Net-(DP8-Pad1)") (class "Default")
      (node (ref "DP8") (pin "1") (pinfunction "1_1") (pintype "passive"))
      (node (ref "RL8") (pin "2") (pinfunction "2_2") (pintype "passive"))
    )
    (net (code "52") (name "Net-(DP9-Pad1)") (class "Default")
      (node (ref "DP9") (pin "1") (pinfunction "1_1") (pintype "passive"))
      (node (ref "RL9") (pin "2") (pinfunction "2_2") (pintype "passive"))
    )
    (net (code "53") (name "Net-(DP10-Pad1)") (class "Default")
      (node (ref "DP10") (pin "1") (pinfunction "1_1") (pintype "passive"))
      (node (ref "RL10") (pin "2") (pinfunction "2_2") (pintype "passive"))
    )
    (net (code "54") (name "Net-(DP11-Pad1)") (class "Default")
      (node (ref "DP11") (pin "1") (pinfunction "1_1") (pintype "passive"))
      (node (ref "RL11") (pin "2") (pinfunction "2_2") (pintype "passive"))
    )
    (net (code "55") (name "Net-(DP12-Pad1)") (class "Default")
      (node (ref "DP12") (pin "1") (pinfunction "1_1") (pintype "passive"))
      (node (ref "RL12") (pin "2") (pinfunction "2_2") (pintype "passive"))
    )
    (net (code "56") (name "Net-(DP13-Pad1)") (class "Default")
      (node (ref "DP13") (pin "1") (pinfunction "1_1") (pintype "passive"))
      (node (ref "RL13") (pin "2") (pinfunction "2_2") (pintype "passive"))
    )
    (net (code "57") (name "Net-(DP14-Pad1)") (class "Default")
      (node (ref "DP14") (pin "1") (pinfunction "1_1") (pintype "passive"))
      (node (ref "RL14") (pin "2") (pinfunction "2_2") (pintype "passive"))
    )
    (net (code "58") (name "Net-(DP15-Pad1)") (class "Default")
      (node (ref "DP15") (pin "1") (pinfunction "1_1") (pintype "passive"))
      (node (ref "RL15") (pin "2") (pinfunction "2_2") (pintype "passive"))
    )
    (net (code "59") (name "Net-(DP16-Pad1)") (class "Default")
      (node (ref "DP16") (pin "1") (pinfunction "1_1") (pintype "passive"))
      (node (ref "RL16") (pin "2") (pinfunction "2_2") (pintype "passive"))
    )
    (net (code "60") (name "Net-(EMI_IN-Signal)") (class "Default")
      (node (ref "C7") (pin "1") (pinfunction "1_1") (pintype "passive"))
      (node (ref "EMI_IN") (pin "1") (pinfunction "Signal_1") (pintype "passive"))
    )
    (net (code "61") (name "Net-(L1-RF)") (class "Default")
      (node (ref "L1") (pin "2") (pinfunction "RF_2") (pintype "passive"))
      (node (ref "LC20") (pin "1") (pintype "passive"))
    )
    (net (code "62") (name "Net-(L1-RF+DC)") (class "Default")
      (node (ref "L1") (pin "1") (pinfunction "RF+DC_1") (pintype "passive"))
      (node (ref "U3") (pin "3") (pinfunction "Gnd_3") (pintype "output"))
    )
    (net (code "63") (name "Net-(L2-RF)") (class "Default")
      (node (ref "L2") (pin "2") (pinfunction "RF_2") (pintype "passive"))
      (node (ref "OUT") (pin "1") (pinfunction "Signal_1") (pintype "passive"))
    )
    (net (code "64") (name "Net-(L2-RF+DC)") (class "Default")
      (node (ref "L2") (pin "1") (pinfunction "RF+DC_1") (pintype "passive"))
      (node (ref "U4") (pin "3") (pinfunction "Gnd_3") (pintype "output"))
    )
    (net (code "65") (name "Net-(L3-Pad2)") (class "Default")
      (node (ref "L3") (pin "2") (pinfunction "2_2") (pintype "passive"))
      (node (ref "R60") (pin "1") (pinfunction "1_1") (pintype "passive"))
    )
    (net (code "66") (name "Net-(L4-Pad2)") (class "Default")
      (node (ref "L4") (pin "2") (pinfunction "2_2") (pintype "passive"))
      (node (ref "R61") (pin "1") (pinfunction "1_1") (pintype "passive"))
    )
    (net (code "67") (name "Net-(OSC-Signal)") (class "Default")
      (node (ref "C27") (pin "1") (pinfunction "1_1") (pintype "passive"))
      (node (ref "OSC") (pin "1") (pinfunction "Signal_1") (pintype "passive"))
    )
    (net (code "68") (name "Net-(T2-A-Signal)") (class "Default")
      (node (ref "T2-A") (pin "1") (pinfunction "Signal_1") (pintype "passive"))
      (node (ref "T2-B") (pin "1") (pinfunction "Signal_1") (pintype "passive"))
    )
    (net (code "69") (name "Net-(TONE-Signal)") (class "Default")
      (node (ref "C1") (pin "1") (pinfunction "1_1") (pintype "passive"))
      (node (ref "TONE") (pin "1") (pinfunction "Signal_1") (pintype "passive"))
    )
    (net (code "70") (name "Net-(U1-Coupled)") (class "Default")
      (node (ref "C16") (pin "2") (pinfunction "2_2") (pintype "passive"))
      (node (ref "U1") (pin "3") (pinfunction "Coupled_3") (pintype "output"))
    )
    (net (code "71") (name "Net-(U1-Input)") (class "Default")
      (node (ref "D1") (pin "7") (pinfunction "Gnd_7") (pintype "output"))
      (node (ref "U1") (pin "1") (pinfunction "Input_1") (pintype "input"))
    )
    (net (code "72") (name "Net-(U1-Output)") (class "Default")
      (node (ref "C3") (pin "1") (pinfunction "1_1") (pintype "passive"))
      (node (ref "U1") (pin "6") (pinfunction "Output_6") (pintype "output"))
    )
    (net (code "73") (name "Net-(U1-Termination)") (class "Default")
      (node (ref "R1") (pin "2") (pinfunction "2_2") (pintype "passive"))
      (node (ref "U1") (pin "4") (pinfunction "Termination_4") (pintype "output"))
    )
    (net (code "74") (name "Net-(U2-IN1)") (class "Default")
      (node (ref "R23") (pin "1") (pinfunction "1_1") (pintype "passive"))
      (node (ref "U2") (pin "7") (pinfunction "IN1_7") (pintype "input"))
    )
    (net (code "75") (name "Net-(U2-IN2)") (class "Default")
      (node (ref "R22") (pin "1") (pinfunction "1_1") (pintype "passive"))
      (node (ref "U2") (pin "6") (pinfunction "IN2_6") (pintype "input"))
    )
    (net (code "76") (name "Net-(U2-IN3)") (class "Default")
      (node (ref "R21") (pin "1") (pinfunction "1_1") (pintype "passive"))
      (node (ref "U2") (pin "5") (pinfunction "IN3_5") (pintype "input"))
    )
    (net (code "77") (name "Net-(U2-RF1)") (class "Default")
      (node (ref "C3") (pin "2") (pinfunction "2_2") (pintype "passive"))
      (node (ref "U2") (pin "3") (pinfunction "RF1_3") (pintype "passive"))
    )
    (net (code "78") (name "Net-(U2-RF2)") (class "Default")
      (node (ref "C19") (pin "2") (pinfunction "2_2") (pintype "passive"))
      (node (ref "U2") (pin "9") (pinfunction "RF2_9") (pintype "passive"))
    )
    (net (code "79") (name "Net-(U2-RF3)") (class "Default")
      (node (ref "C7") (pin "2") (pinfunction "2_2") (pintype "passive"))
      (node (ref "U2") (pin "2") (pinfunction "RF3_2") (pintype "passive"))
    )
    (net (code "80") (name "Net-(U2-RF4)") (class "Default")
      (node (ref "C2") (pin "2") (pinfunction "2_2") (pintype "passive"))
      (node (ref "U2") (pin "10") (pinfunction "RF4_10") (pintype "passive"))
    )
    (net (code "81") (name "Net-(U2-RF5)") (class "Default")
      (node (ref "C4") (pin "2") (pinfunction "2_2") (pintype "passive"))
      (node (ref "U2") (pin "1") (pinfunction "RF5_1") (pintype "passive"))
    )
    (net (code "82") (name "Net-(U2-RF6)") (class "Default")
      (node (ref "C6") (pin "2") (pinfunction "2_2") (pintype "passive"))
      (node (ref "U2") (pin "11") (pinfunction "RF6_11") (pintype "passive"))
    )
    (net (code "83") (name "Net-(U2-RF_COM)") (class "Default")
      (node (ref "C8") (pin "1") (pinfunction "1_1") (pintype "passive"))
      (node (ref "U2") (pin "13") (pinfunction "RF_COM_13") (pintype "passive"))
    )
    (net (code "84") (name "Net-(U2-Vdd)") (class "Default")
      (node (ref "R20") (pin "1") (pinfunction "1_1") (pintype "passive"))
      (node (ref "U2") (pin "4") (pinfunction "Vdd_4") (pintype "power_in"))
    )
    (net (code "85") (name "Net-(U3-In)") (class "Default")
      (node (ref "C8") (pin "2") (pinfunction "2_2") (pintype "passive"))
      (node (ref "L3") (pin "1") (pinfunction "1_1") (pintype "passive"))
      (node (ref "U3") (pin "1") (pinfunction "In_1") (pintype "input"))
    )
    (net (code "86") (name "Net-(U4-In)") (class "Default")
      (node (ref "C14") (pin "2") (pinfunction "2_2") (pintype "passive"))
      (node (ref "L4") (pin "1") (pinfunction "1_1") (pintype "passive"))
      (node (ref "U4") (pin "1") (pinfunction "In_1") (pintype "input"))
    )
    (net (code "87") (name "Net-(U8-Control)") (class "Default")
      (node (ref "R24") (pin "2") (pinfunction "2_2") (pintype "passive"))
      (node (ref "U8") (pin "7") (pinfunction "Control_7") (pintype "input"))
    )
    (net (code "88") (name "Net-(U8-Enable)") (class "Default")
      (node (ref "R25") (pin "2") (pinfunction "2_2") (pintype "passive"))
      (node (ref "U8") (pin "8") (pinfunction "Enable_8") (pintype "input"))
    )
    (net (code "89") (name "Net-(U8-RF1)") (class "Default")
      (node (ref "C15") (pin "1") (pinfunction "1_1") (pintype "passive"))
      (node (ref "U8") (pin "11") (pinfunction "RF1_11") (pintype "bidirectional"))
    )
    (net (code "90") (name "Net-(U8-RF2)") (class "Default")
      (node (ref "C17") (pin "1") (pinfunction "1_1") (pintype "passive"))
      (node (ref "U8") (pin "5") (pinfunction "RF2_5") (pintype "bidirectional"))
    )
    (net (code "91") (name "Net-(U8-RFCOM)") (class "Default")
      (node (ref "C27") (pin "2") (pinfunction "2_2") (pintype "passive"))
      (node (ref "U8") (pin "2") (pinfunction "RFCOM_2") (pintype "bidirectional"))
    )
    (net (code "92") (name "Net-(U8-Vdd)") (class "Default")
      (node (ref "R31") (pin "1") (pinfunction "1_1") (pintype "passive"))
      (node (ref "U8") (pin "9") (pinfunction "Vdd_9") (pintype "power_in"))
    )
    (net (code "93") (name "Net-(U10-QF)") (class "Default")
      (node (ref "RL6") (pin "1") (pinfunction "1_1") (pintype "passive"))
      (node (ref "U10") (pin "5") (pinfunction "QF_5") (pintype "tri_state"))
    )
    (net (code "94") (name "unconnected-(L1-NC-Pad4)") (class "Default")
      (node (ref "L1") (pin "4") (pinfunction "NC_4") (pintype "passive"))
    )
    (net (code "95") (name "unconnected-(L2-NC-Pad4)") (class "Default")
      (node (ref "L2") (pin "4") (pinfunction "NC_4") (pintype "passive"))
    )
    (net (code "96") (name "unconnected-(U1-DNC-Pad5)") (class "Default")
      (node (ref "U1") (pin "5") (pinfunction "DNC_5") (pintype "passive"))
    )
    (net (code "97") (name "unconnected-(U2-NC-Pad8)") (class "Default")
      (node (ref "U2") (pin "8") (pinfunction "NC_8") (pintype "passive+no_connect"))
    )
    (net (code "98") (name "unconnected-(U2-NC-Pad12)") (class "Default")
      (node (ref "U2") (pin "12") (pinfunction "NC_12") (pintype "passive+no_connect"))
    )
    (net (code "99") (name "unconnected-(U2-NC-Pad14)") (class "Default")
      (node (ref "U2") (pin "14") (pinfunction "NC_14") (pintype "passive+no_connect"))
    )
    (net (code "100") (name "unconnected-(U10-QH'-Pad9)") (class "Default")
      (node (ref "U10") (pin "9") (pinfunction "QH'_9") (pintype "output"))
    )
  )
)
